# SCH_Bike-Helmet-Turn-Signals_2024-05-09.net
KiCad netlist of a schematic drawn in EasyEDA
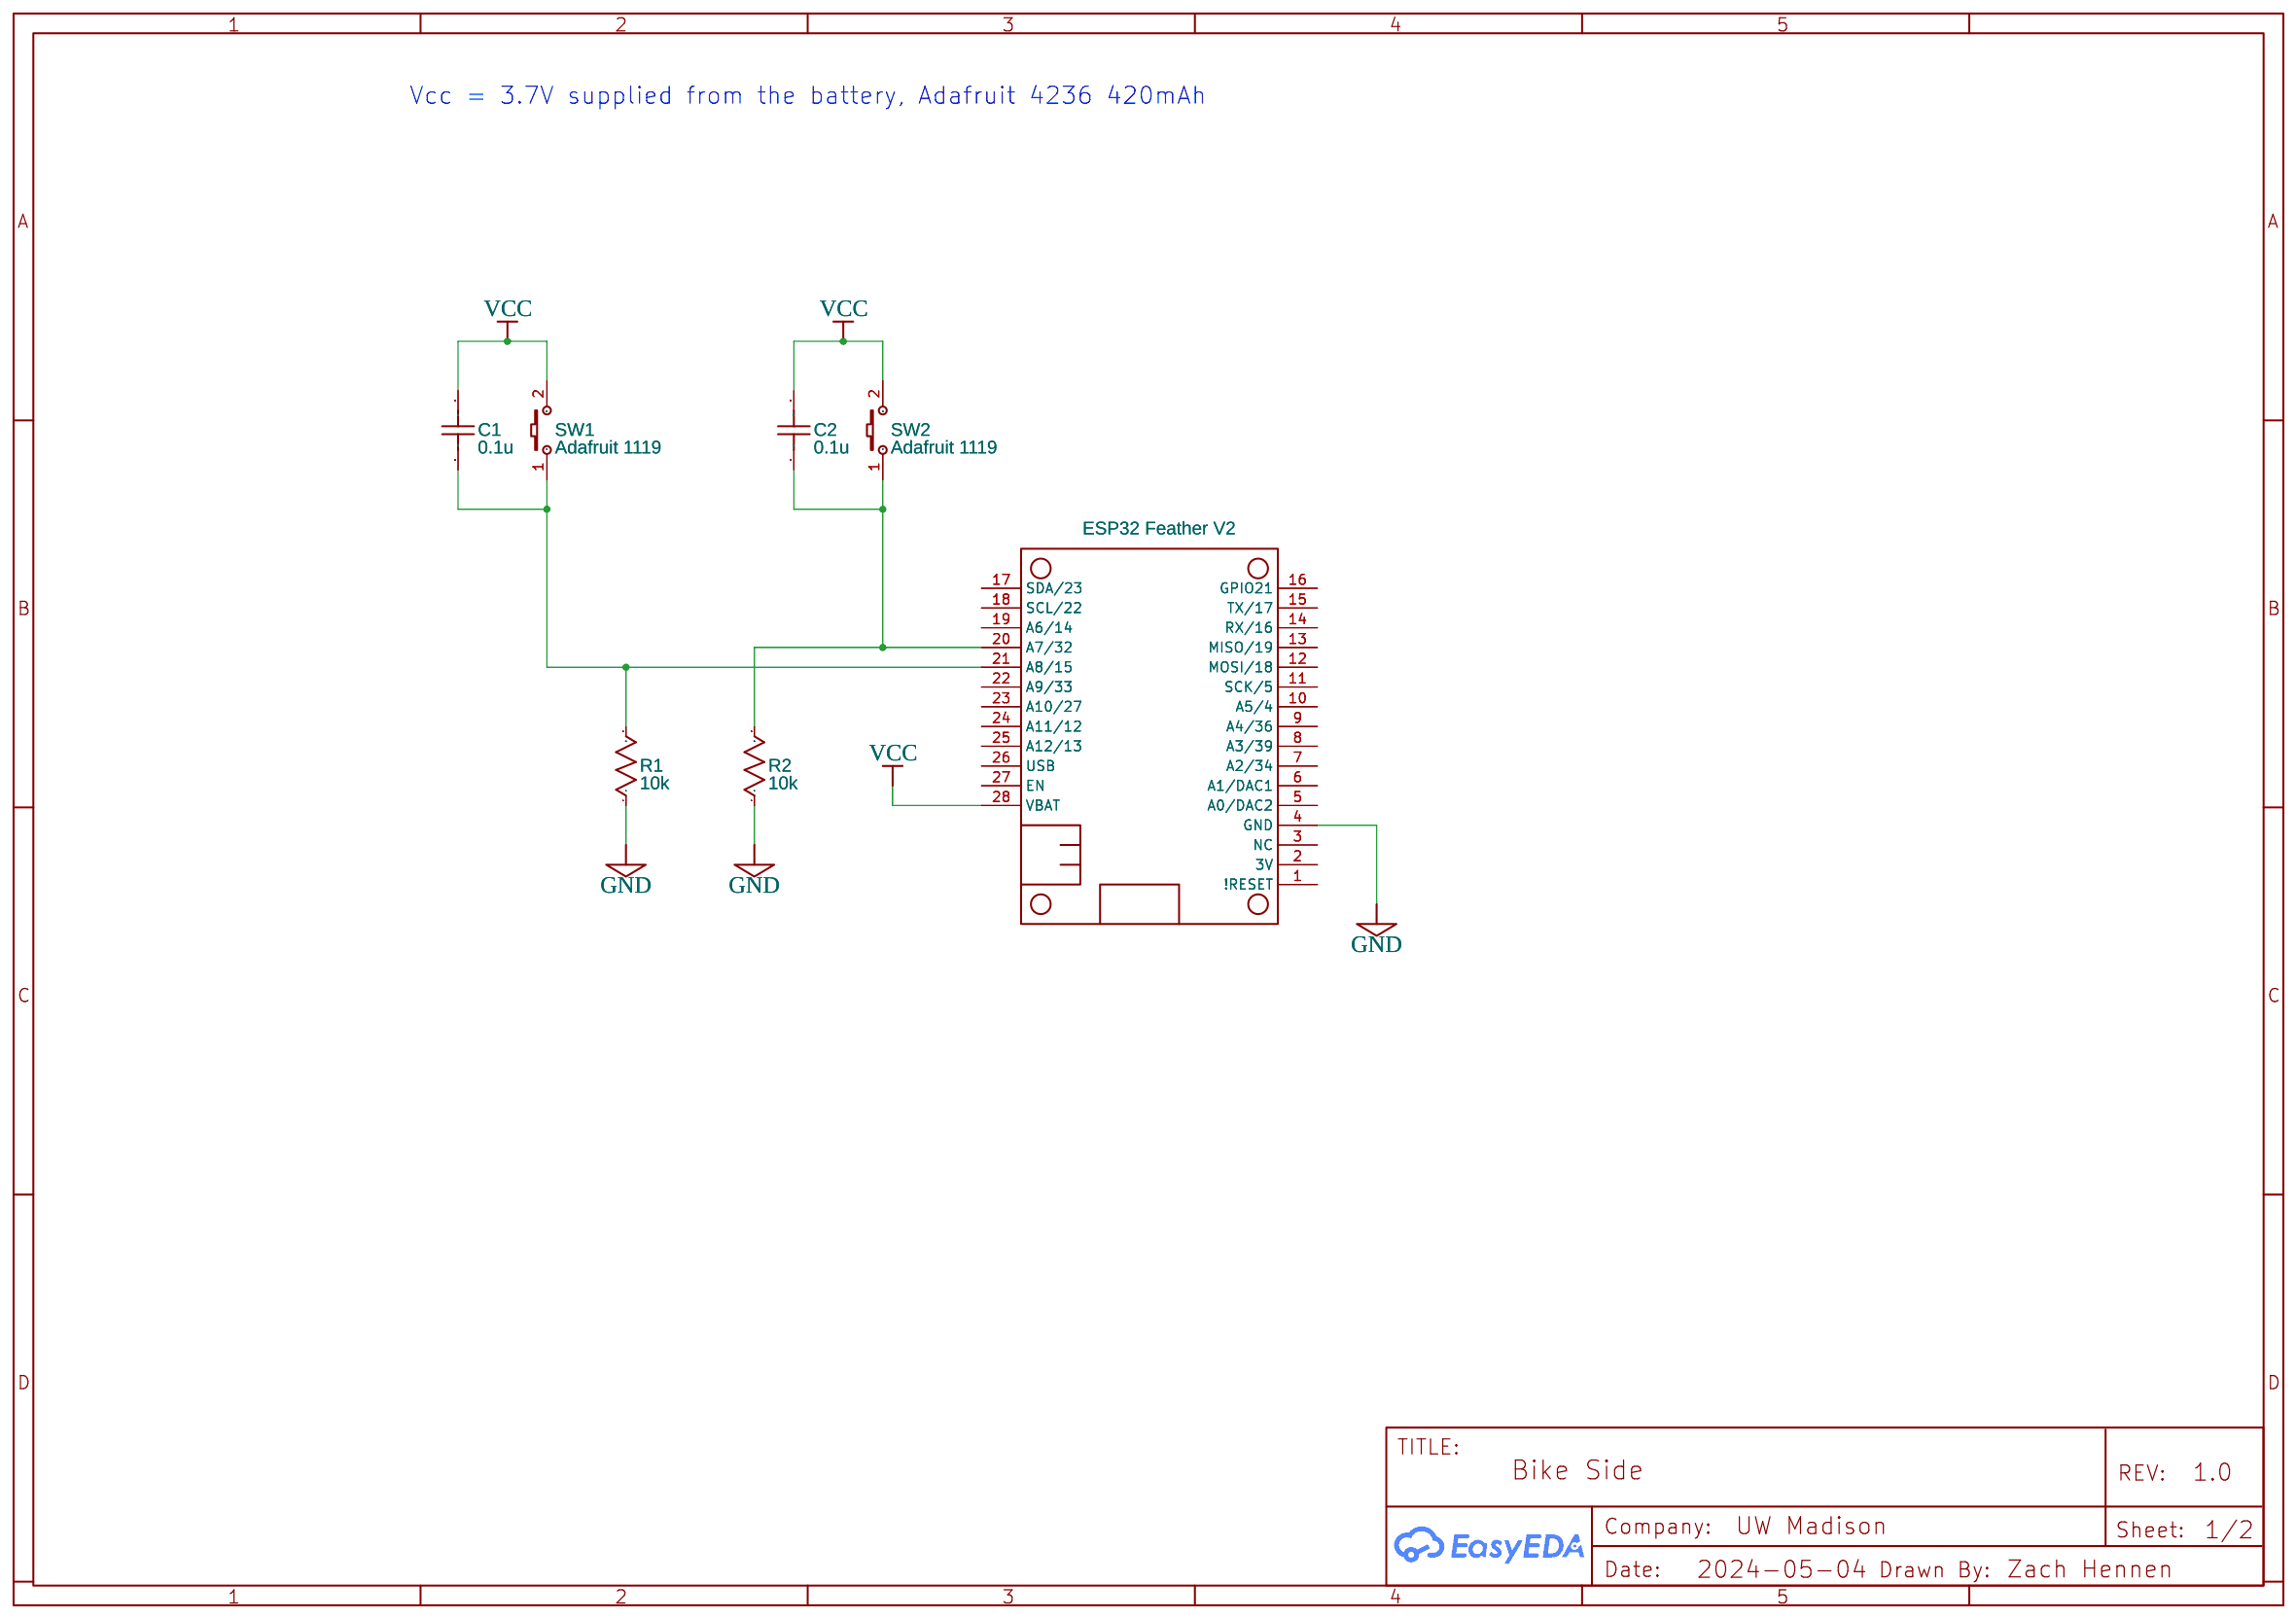
[diagram p0: Sheet_1]
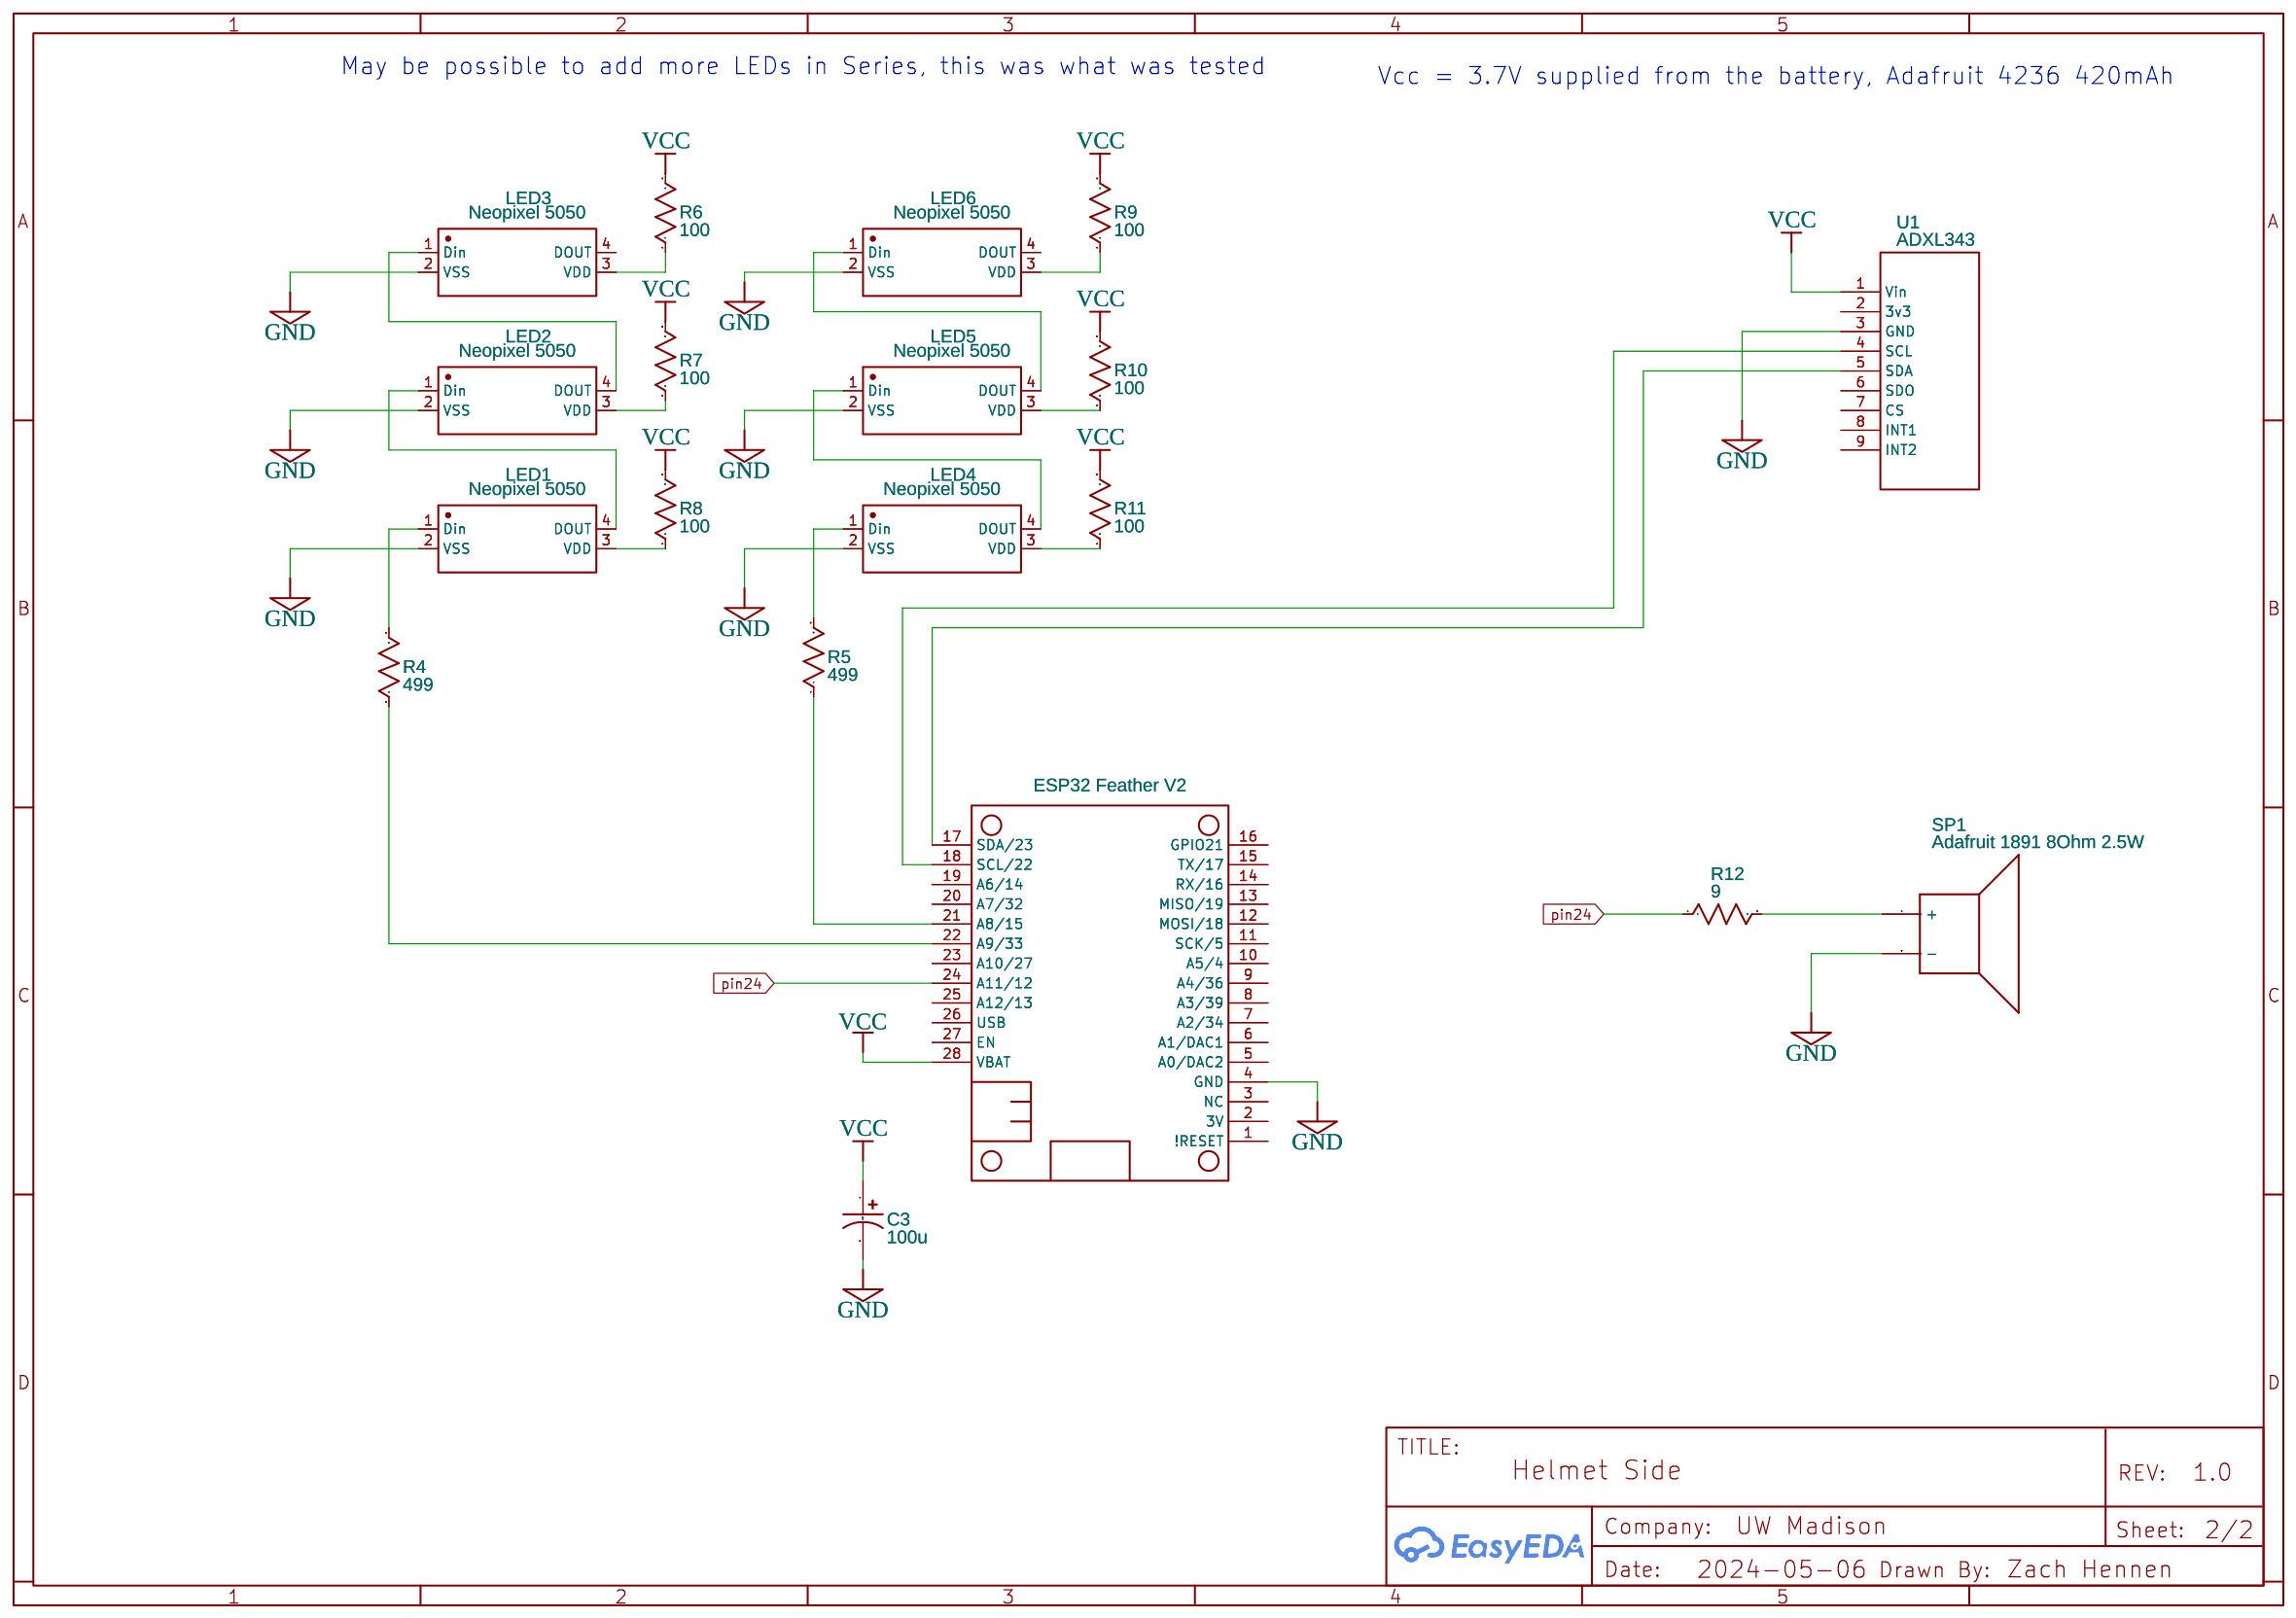
[diagram p1: Sheet_2]

(export (version "E")
  (design (tool "Eeschema 10.0.6"))
  (components
    (comp (ref "C1") (value "0.1u") (libsource (lib "") (part "C_0603_US")))
    (comp (ref "C2") (value "0.1u") (libsource (lib "") (part "C_0603_US")))
    (comp (ref "MS2") (value "ESP32 Feather V2") (libsource (lib "") (part "Feather_HUZZAH32 small outline")))
    (comp (ref "R1") (value "10k") (libsource (lib "") (part "R_0603_US")))
    (comp (ref "R2") (value "10k") (libsource (lib "") (part "R_0603_US")))
    (comp (ref "SW1")
      (value "Adafruit 1119")
      (fields (field (name "Manufacturer Part") "K2-1107ST-A4SW-06"))
      (libsource (lib "") (part "K2-3.6×6.1_SMD"))
    )
    (comp (ref "SW2")
      (value "Adafruit 1119")
      (fields (field (name "Manufacturer Part") "K2-1107ST-A4SW-06"))
      (libsource (lib "") (part "K2-3.6×6.1_SMD"))
    )
    (comp (ref "C3") (value "100u") (libsource (lib "") (part "C_Tan_SMD_A_US")))
    (comp (ref "LED1") (value "Neopixel 5050") (libsource (lib "") (part "5050")))
    (comp (ref "LED2") (value "Neopixel 5050") (libsource (lib "") (part "5050")))
    (comp (ref "LED3") (value "Neopixel 5050") (libsource (lib "") (part "5050")))
    (comp (ref "LED4") (value "Neopixel 5050") (libsource (lib "") (part "5050")))
    (comp (ref "LED5") (value "Neopixel 5050") (libsource (lib "") (part "5050")))
    (comp (ref "LED6") (value "Neopixel 5050") (libsource (lib "") (part "5050")))
    (comp (ref "MS1") (value "ESP32 Feather V2") (libsource (lib "") (part "Feather_HUZZAH32 small outline")))
    (comp (ref "R4") (value "499") (libsource (lib "") (part "R_0603_US")))
    (comp (ref "R5") (value "499") (libsource (lib "") (part "R_0603_US")))
    (comp (ref "R6") (value "100") (libsource (lib "") (part "R_0603_US")))
    (comp (ref "R7") (value "100") (libsource (lib "") (part "R_0603_US")))
    (comp (ref "R8") (value "100") (libsource (lib "") (part "R_0603_US")))
    (comp (ref "R9") (value "100") (libsource (lib "") (part "R_0603_US")))
    (comp (ref "R10") (value "100") (libsource (lib "") (part "R_0603_US")))
    (comp (ref "R11") (value "100") (libsource (lib "") (part "R_0603_US")))
    (comp (ref "R12") (value "9") (libsource (lib "") (part "R_0603_US_1")))
    (comp (ref "SP1") (value "Adafruit 1891 8Ohm 2.5W") (libsource (lib "") (part "SPEAKER")))
    (comp (ref "U1") (value "ADXL343") (libsource (lib "") (part "ADXL343")))
  )
  (nets
    (net (code "1") (name "GND") (class "Default")
      (node (ref "C3") (pin "2") (pinfunction "2_2") (pintype "unspecified"))
      (node (ref "LED1") (pin "2") (pinfunction "VSS_2") (pintype "unspecified"))
      (node (ref "LED2") (pin "2") (pinfunction "VSS_2") (pintype "unspecified"))
      (node (ref "LED3") (pin "2") (pinfunction "VSS_2") (pintype "unspecified"))
      (node (ref "LED4") (pin "2") (pinfunction "VSS_2") (pintype "unspecified"))
      (node (ref "LED5") (pin "2") (pinfunction "VSS_2") (pintype "unspecified"))
      (node (ref "LED6") (pin "2") (pinfunction "VSS_2") (pintype "unspecified"))
      (node (ref "MS1") (pin "4") (pinfunction "GND_4") (pintype "passive"))
      (node (ref "MS2") (pin "4") (pinfunction "GND_4") (pintype "passive"))
      (node (ref "R1") (pin "1") (pinfunction "1_1") (pintype "unspecified"))
      (node (ref "R2") (pin "1") (pinfunction "1_1") (pintype "unspecified"))
      (node (ref "SP1") (pin "2") (pinfunction "-_2") (pintype "bidirectional"))
      (node (ref "U1") (pin "3") (pinfunction "GND_3") (pintype "unspecified"))
    )
    (net (code "2") (name "Net-(LED1-DOUT)") (class "Default")
      (node (ref "LED1") (pin "4") (pinfunction "DOUT_4") (pintype "unspecified"))
      (node (ref "LED2") (pin "1") (pinfunction "Din_1") (pintype "unspecified"))
    )
    (net (code "3") (name "Net-(LED1-Din)") (class "Default")
      (node (ref "LED1") (pin "1") (pinfunction "Din_1") (pintype "unspecified"))
      (node (ref "R4") (pin "2") (pinfunction "2_2") (pintype "unspecified"))
    )
    (net (code "4") (name "Net-(LED1-VDD)") (class "Default")
      (node (ref "LED1") (pin "3") (pinfunction "VDD_3") (pintype "unspecified"))
      (node (ref "R8") (pin "1") (pinfunction "1_1") (pintype "unspecified"))
    )
    (net (code "5") (name "Net-(LED2-DOUT)") (class "Default")
      (node (ref "LED2") (pin "4") (pinfunction "DOUT_4") (pintype "unspecified"))
      (node (ref "LED3") (pin "1") (pinfunction "Din_1") (pintype "unspecified"))
    )
    (net (code "6") (name "Net-(LED2-VDD)") (class "Default")
      (node (ref "LED2") (pin "3") (pinfunction "VDD_3") (pintype "unspecified"))
      (node (ref "R7") (pin "1") (pinfunction "1_1") (pintype "unspecified"))
    )
    (net (code "7") (name "Net-(LED3-VDD)") (class "Default")
      (node (ref "LED3") (pin "3") (pinfunction "VDD_3") (pintype "unspecified"))
      (node (ref "R6") (pin "1") (pinfunction "1_1") (pintype "unspecified"))
    )
    (net (code "8") (name "Net-(LED4-DOUT)") (class "Default")
      (node (ref "LED4") (pin "4") (pinfunction "DOUT_4") (pintype "unspecified"))
      (node (ref "LED5") (pin "1") (pinfunction "Din_1") (pintype "unspecified"))
    )
    (net (code "9") (name "Net-(LED4-Din)") (class "Default")
      (node (ref "LED4") (pin "1") (pinfunction "Din_1") (pintype "unspecified"))
      (node (ref "R5") (pin "2") (pinfunction "2_2") (pintype "unspecified"))
    )
    (net (code "10") (name "Net-(LED4-VDD)") (class "Default")
      (node (ref "LED4") (pin "3") (pinfunction "VDD_3") (pintype "unspecified"))
      (node (ref "R11") (pin "1") (pinfunction "1_1") (pintype "unspecified"))
    )
    (net (code "11") (name "Net-(LED5-DOUT)") (class "Default")
      (node (ref "LED5") (pin "4") (pinfunction "DOUT_4") (pintype "unspecified"))
      (node (ref "LED6") (pin "1") (pinfunction "Din_1") (pintype "unspecified"))
    )
    (net (code "12") (name "Net-(LED5-VDD)") (class "Default")
      (node (ref "LED5") (pin "3") (pinfunction "VDD_3") (pintype "unspecified"))
      (node (ref "R10") (pin "1") (pinfunction "1_1") (pintype "unspecified"))
    )
    (net (code "13") (name "Net-(LED6-VDD)") (class "Default")
      (node (ref "LED6") (pin "3") (pinfunction "VDD_3") (pintype "unspecified"))
      (node (ref "R9") (pin "1") (pinfunction "1_1") (pintype "unspecified"))
    )
    (net (code "14") (name "Net-(MS1-A8{slash}15)") (class "Default")
      (node (ref "MS1") (pin "21") (pinfunction "A8/15_21") (pintype "unspecified"))
      (node (ref "R5") (pin "1") (pinfunction "1_1") (pintype "unspecified"))
    )
    (net (code "15") (name "Net-(MS1-A9{slash}33)") (class "Default")
      (node (ref "MS1") (pin "22") (pinfunction "A9/33_22") (pintype "unspecified"))
      (node (ref "R4") (pin "1") (pinfunction "1_1") (pintype "unspecified"))
    )
    (net (code "16") (name "Net-(MS1-SCL{slash}22)") (class "Default")
      (node (ref "MS1") (pin "18") (pinfunction "SCL/22_18") (pintype "unspecified"))
      (node (ref "U1") (pin "4") (pinfunction "SCL_4") (pintype "unspecified"))
    )
    (net (code "17") (name "Net-(MS1-SDA{slash}23)") (class "Default")
      (node (ref "MS1") (pin "17") (pinfunction "SDA/23_17") (pintype "unspecified"))
      (node (ref "U1") (pin "5") (pinfunction "SDA_5") (pintype "unspecified"))
    )
    (net (code "18") (name "Net-(MS2-A7{slash}32)") (class "Default")
      (node (ref "C2") (pin "1") (pinfunction "1_1") (pintype "unspecified"))
      (node (ref "MS2") (pin "20") (pinfunction "A7/32_20") (pintype "unspecified"))
      (node (ref "R2") (pin "2") (pinfunction "2_2") (pintype "unspecified"))
      (node (ref "SW2") (pin "1") (pinfunction "1_1") (pintype "unspecified"))
    )
    (net (code "19") (name "Net-(MS2-A8{slash}15)") (class "Default")
      (node (ref "C1") (pin "1") (pinfunction "1_1") (pintype "unspecified"))
      (node (ref "MS2") (pin "21") (pinfunction "A8/15_21") (pintype "unspecified"))
      (node (ref "R1") (pin "2") (pinfunction "2_2") (pintype "unspecified"))
      (node (ref "SW1") (pin "1") (pinfunction "1_1") (pintype "unspecified"))
    )
    (net (code "20") (name "Net-(SP1-+)") (class "Default")
      (node (ref "R12") (pin "2") (pinfunction "2_2") (pintype "unspecified"))
      (node (ref "SP1") (pin "1") (pinfunction "+_1") (pintype "bidirectional"))
    )
    (net (code "21") (name "VCC") (class "Default")
      (node (ref "C1") (pin "2") (pinfunction "2_2") (pintype "unspecified"))
      (node (ref "C2") (pin "2") (pinfunction "2_2") (pintype "unspecified"))
      (node (ref "C3") (pin "1") (pinfunction "1_1") (pintype "unspecified"))
      (node (ref "MS1") (pin "28") (pinfunction "VBAT_28") (pintype "unspecified"))
      (node (ref "MS2") (pin "28") (pinfunction "VBAT_28") (pintype "unspecified"))
      (node (ref "R10") (pin "2") (pinfunction "2_2") (pintype "unspecified"))
      (node (ref "R11") (pin "2") (pinfunction "2_2") (pintype "unspecified"))
      (node (ref "R6") (pin "2") (pinfunction "2_2") (pintype "unspecified"))
      (node (ref "R7") (pin "2") (pinfunction "2_2") (pintype "unspecified"))
      (node (ref "R8") (pin "2") (pinfunction "2_2") (pintype "unspecified"))
      (node (ref "R9") (pin "2") (pinfunction "2_2") (pintype "unspecified"))
      (node (ref "SW1") (pin "2") (pinfunction "2_2") (pintype "unspecified"))
      (node (ref "SW2") (pin "2") (pinfunction "2_2") (pintype "unspecified"))
      (node (ref "U1") (pin "1") (pinfunction "Vin_1") (pintype "unspecified"))
    )
    (net (code "22") (name "pin24") (class "Default")
      (node (ref "MS1") (pin "24") (pinfunction "A11/12_24") (pintype "unspecified"))
      (node (ref "R12") (pin "1") (pinfunction "1_1") (pintype "unspecified"))
    )
    (net (code "23") (name "unconnected-(LED3-DOUT-Pad4)") (class "Default")
      (node (ref "LED3") (pin "4") (pinfunction "DOUT_4") (pintype "unspecified"))
    )
    (net (code "24") (name "unconnected-(LED6-DOUT-Pad4)") (class "Default")
      (node (ref "LED6") (pin "4") (pinfunction "DOUT_4") (pintype "unspecified"))
    )
    (net (code "25") (name "unconnected-(MS1-!RESET-Pad1)") (class "Default")
      (node (ref "MS1") (pin "1") (pinfunction "!RESET_1") (pintype "input"))
    )
    (net (code "26") (name "unconnected-(MS1-3V-Pad2)") (class "Default")
      (node (ref "MS1") (pin "2") (pinfunction "3V_2") (pintype "unspecified"))
    )
    (net (code "27") (name "unconnected-(MS1-A0{slash}DAC2-Pad5)") (class "Default")
      (node (ref "MS1") (pin "5") (pinfunction "A0/DAC2_5") (pintype "unspecified"))
    )
    (net (code "28") (name "unconnected-(MS1-A1{slash}DAC1-Pad6)") (class "Default")
      (node (ref "MS1") (pin "6") (pinfunction "A1/DAC1_6") (pintype "unspecified"))
    )
    (net (code "29") (name "unconnected-(MS1-A2{slash}34-Pad7)") (class "Default")
      (node (ref "MS1") (pin "7") (pinfunction "A2/34_7") (pintype "unspecified"))
    )
    (net (code "30") (name "unconnected-(MS1-A3{slash}39-Pad8)") (class "Default")
      (node (ref "MS1") (pin "8") (pinfunction "A3/39_8") (pintype "unspecified"))
    )
    (net (code "31") (name "unconnected-(MS1-A4{slash}36-Pad9)") (class "Default")
      (node (ref "MS1") (pin "9") (pinfunction "A4/36_9") (pintype "unspecified"))
    )
    (net (code "32") (name "unconnected-(MS1-A5{slash}4-Pad10)") (class "Default")
      (node (ref "MS1") (pin "10") (pinfunction "A5/4_10") (pintype "unspecified"))
    )
    (net (code "33") (name "unconnected-(MS1-A6{slash}14-Pad19)") (class "Default")
      (node (ref "MS1") (pin "19") (pinfunction "A6/14_19") (pintype "unspecified"))
    )
    (net (code "34") (name "unconnected-(MS1-A7{slash}32-Pad20)") (class "Default")
      (node (ref "MS1") (pin "20") (pinfunction "A7/32_20") (pintype "unspecified"))
    )
    (net (code "35") (name "unconnected-(MS1-A10{slash}27-Pad23)") (class "Default")
      (node (ref "MS1") (pin "23") (pinfunction "A10/27_23") (pintype "unspecified"))
    )
    (net (code "36") (name "unconnected-(MS1-A12{slash}13-Pad25)") (class "Default")
      (node (ref "MS1") (pin "25") (pinfunction "A12/13_25") (pintype "unspecified"))
    )
    (net (code "37") (name "unconnected-(MS1-EN-Pad27)") (class "Default")
      (node (ref "MS1") (pin "27") (pinfunction "EN_27") (pintype "unspecified"))
    )
    (net (code "38") (name "unconnected-(MS1-GPIO21-Pad16)") (class "Default")
      (node (ref "MS1") (pin "16") (pinfunction "GPIO21_16") (pintype "unspecified"))
    )
    (net (code "39") (name "unconnected-(MS1-MISO{slash}19-Pad13)") (class "Default")
      (node (ref "MS1") (pin "13") (pinfunction "MISO/19_13") (pintype "unspecified"))
    )
    (net (code "40") (name "unconnected-(MS1-MOSI{slash}18-Pad12)") (class "Default")
      (node (ref "MS1") (pin "12") (pinfunction "MOSI/18_12") (pintype "unspecified"))
    )
    (net (code "41") (name "unconnected-(MS1-NC-Pad3)") (class "Default")
      (node (ref "MS1") (pin "3") (pinfunction "NC_3") (pintype "unspecified"))
    )
    (net (code "42") (name "unconnected-(MS1-RX{slash}16-Pad14)") (class "Default")
      (node (ref "MS1") (pin "14") (pinfunction "RX/16_14") (pintype "unspecified"))
    )
    (net (code "43") (name "unconnected-(MS1-SCK{slash}5-Pad11)") (class "Default")
      (node (ref "MS1") (pin "11") (pinfunction "SCK/5_11") (pintype "unspecified"))
    )
    (net (code "44") (name "unconnected-(MS1-TX{slash}17-Pad15)") (class "Default")
      (node (ref "MS1") (pin "15") (pinfunction "TX/17_15") (pintype "unspecified"))
    )
    (net (code "45") (name "unconnected-(MS1-USB-Pad26)") (class "Default")
      (node (ref "MS1") (pin "26") (pinfunction "USB_26") (pintype "unspecified"))
    )
    (net (code "46") (name "unconnected-(MS2-!RESET-Pad1)") (class "Default")
      (node (ref "MS2") (pin "1") (pinfunction "!RESET_1") (pintype "input"))
    )
    (net (code "47") (name "unconnected-(MS2-3V-Pad2)") (class "Default")
      (node (ref "MS2") (pin "2") (pinfunction "3V_2") (pintype "unspecified"))
    )
    (net (code "48") (name "unconnected-(MS2-A0{slash}DAC2-Pad5)") (class "Default")
      (node (ref "MS2") (pin "5") (pinfunction "A0/DAC2_5") (pintype "unspecified"))
    )
    (net (code "49") (name "unconnected-(MS2-A1{slash}DAC1-Pad6)") (class "Default")
      (node (ref "MS2") (pin "6") (pinfunction "A1/DAC1_6") (pintype "unspecified"))
    )
    (net (code "50") (name "unconnected-(MS2-A2{slash}34-Pad7)") (class "Default")
      (node (ref "MS2") (pin "7") (pinfunction "A2/34_7") (pintype "unspecified"))
    )
    (net (code "51") (name "unconnected-(MS2-A3{slash}39-Pad8)") (class "Default")
      (node (ref "MS2") (pin "8") (pinfunction "A3/39_8") (pintype "unspecified"))
    )
    (net (code "52") (name "unconnected-(MS2-A4{slash}36-Pad9)") (class "Default")
      (node (ref "MS2") (pin "9") (pinfunction "A4/36_9") (pintype "unspecified"))
    )
    (net (code "53") (name "unconnected-(MS2-A5{slash}4-Pad10)") (class "Default")
      (node (ref "MS2") (pin "10") (pinfunction "A5/4_10") (pintype "unspecified"))
    )
    (net (code "54") (name "unconnected-(MS2-A6{slash}14-Pad19)") (class "Default")
      (node (ref "MS2") (pin "19") (pinfunction "A6/14_19") (pintype "unspecified"))
    )
    (net (code "55") (name "unconnected-(MS2-A9{slash}33-Pad22)") (class "Default")
      (node (ref "MS2") (pin "22") (pinfunction "A9/33_22") (pintype "unspecified"))
    )
    (net (code "56") (name "unconnected-(MS2-A10{slash}27-Pad23)") (class "Default")
      (node (ref "MS2") (pin "23") (pinfunction "A10/27_23") (pintype "unspecified"))
    )
    (net (code "57") (name "unconnected-(MS2-A11{slash}12-Pad24)") (class "Default")
      (node (ref "MS2") (pin "24") (pinfunction "A11/12_24") (pintype "unspecified"))
    )
    (net (code "58") (name "unconnected-(MS2-A12{slash}13-Pad25)") (class "Default")
      (node (ref "MS2") (pin "25") (pinfunction "A12/13_25") (pintype "unspecified"))
    )
    (net (code "59") (name "unconnected-(MS2-EN-Pad27)") (class "Default")
      (node (ref "MS2") (pin "27") (pinfunction "EN_27") (pintype "unspecified"))
    )
    (net (code "60") (name "unconnected-(MS2-GPIO21-Pad16)") (class "Default")
      (node (ref "MS2") (pin "16") (pinfunction "GPIO21_16") (pintype "unspecified"))
    )
    (net (code "61") (name "unconnected-(MS2-MISO{slash}19-Pad13)") (class "Default")
      (node (ref "MS2") (pin "13") (pinfunction "MISO/19_13") (pintype "unspecified"))
    )
    (net (code "62") (name "unconnected-(MS2-MOSI{slash}18-Pad12)") (class "Default")
      (node (ref "MS2") (pin "12") (pinfunction "MOSI/18_12") (pintype "unspecified"))
    )
    (net (code "63") (name "unconnected-(MS2-NC-Pad3)") (class "Default")
      (node (ref "MS2") (pin "3") (pinfunction "NC_3") (pintype "unspecified"))
    )
    (net (code "64") (name "unconnected-(MS2-RX{slash}16-Pad14)") (class "Default")
      (node (ref "MS2") (pin "14") (pinfunction "RX/16_14") (pintype "unspecified"))
    )
    (net (code "65") (name "unconnected-(MS2-SCK{slash}5-Pad11)") (class "Default")
      (node (ref "MS2") (pin "11") (pinfunction "SCK/5_11") (pintype "unspecified"))
    )
    (net (code "66") (name "unconnected-(MS2-SCL{slash}22-Pad18)") (class "Default")
      (node (ref "MS2") (pin "18") (pinfunction "SCL/22_18") (pintype "unspecified"))
    )
    (net (code "67") (name "unconnected-(MS2-SDA{slash}23-Pad17)") (class "Default")
      (node (ref "MS2") (pin "17") (pinfunction "SDA/23_17") (pintype "unspecified"))
    )
    (net (code "68") (name "unconnected-(MS2-TX{slash}17-Pad15)") (class "Default")
      (node (ref "MS2") (pin "15") (pinfunction "TX/17_15") (pintype "unspecified"))
    )
    (net (code "69") (name "unconnected-(MS2-USB-Pad26)") (class "Default")
      (node (ref "MS2") (pin "26") (pinfunction "USB_26") (pintype "unspecified"))
    )
    (net (code "70") (name "unconnected-(U1-3v3-Pad2)") (class "Default")
      (node (ref "U1") (pin "2") (pinfunction "3v3_2") (pintype "unspecified"))
    )
    (net (code "71") (name "unconnected-(U1-CS-Pad7)") (class "Default")
      (node (ref "U1") (pin "7") (pinfunction "CS_7") (pintype "unspecified"))
    )
    (net (code "72") (name "unconnected-(U1-INT1-Pad8)") (class "Default")
      (node (ref "U1") (pin "8") (pinfunction "INT1_8") (pintype "unspecified"))
    )
    (net (code "73") (name "unconnected-(U1-INT2-Pad9)") (class "Default")
      (node (ref "U1") (pin "9") (pinfunction "INT2_9") (pintype "unspecified"))
    )
    (net (code "74") (name "unconnected-(U1-SDO-Pad6)") (class "Default")
      (node (ref "U1") (pin "6") (pinfunction "SDO_6") (pintype "unspecified"))
    )
  )
)
